# MainSheet.net
KiCad netlist of a schematic drawn in Altium Designer
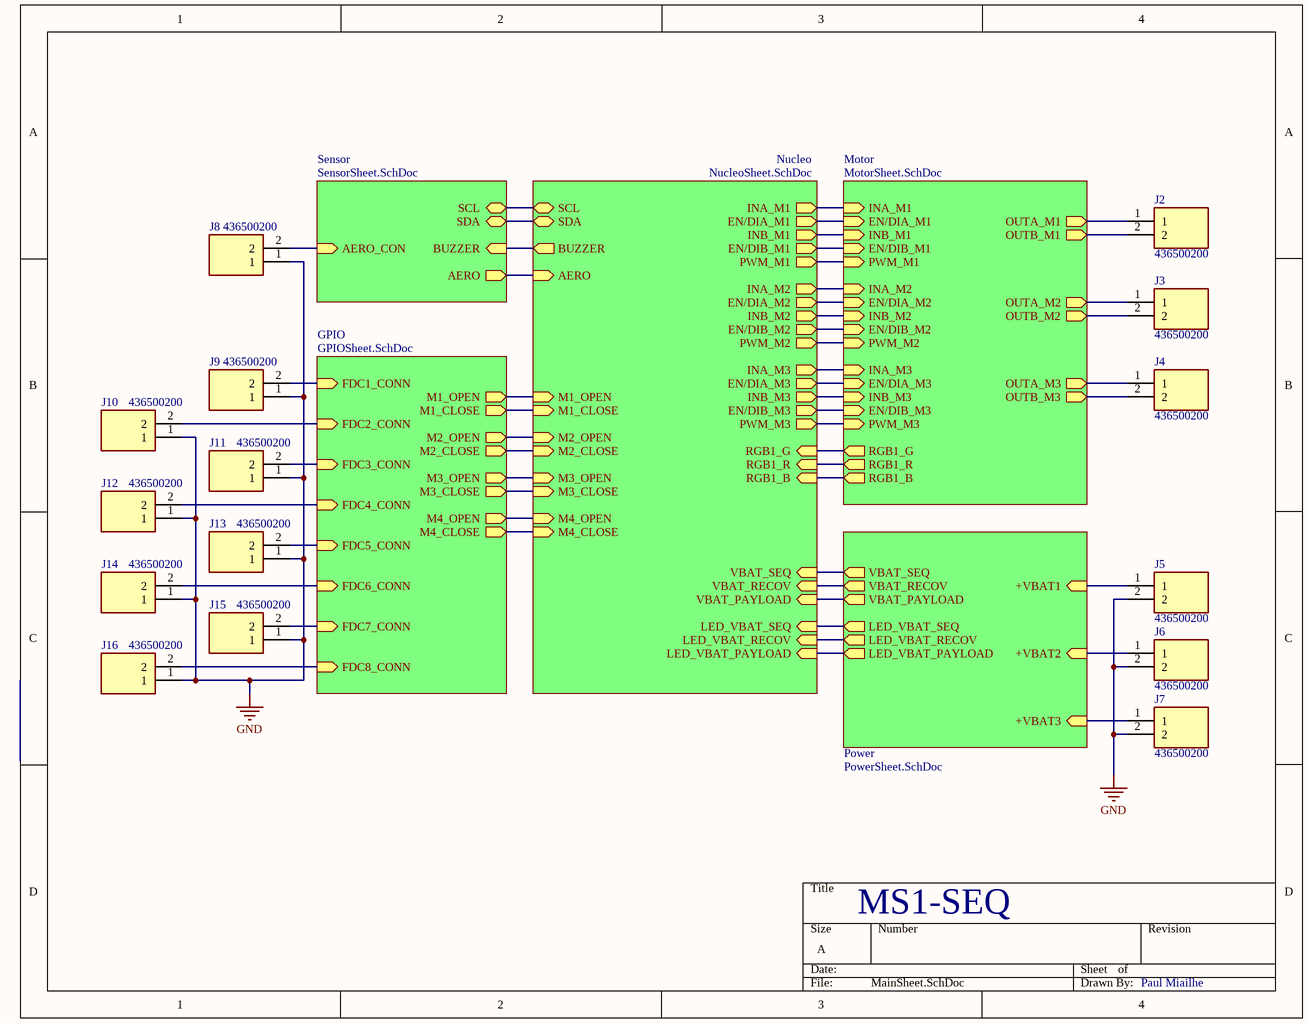
[diagram p0: MainSheet.SchDoc]

(export (version "E")
  (design (tool "Eeschema 10.0.6"))
  (components
    (comp (ref "J2")
      (value "436500200")
      (footprint "43650-0200:MOLEX_436500200")
      (fields (field (name "MF") "{'manufacturer': u'Molex'}"))
      (libsource (lib "*") (part "436500200"))
    )
    (comp (ref "J3")
      (value "436500200")
      (footprint "43650-0200:MOLEX_436500200")
      (fields (field (name "MF") "{'manufacturer': u'Molex'}"))
      (libsource (lib "*") (part "436500200"))
    )
    (comp (ref "J4")
      (value "436500200")
      (footprint "43650-0200:MOLEX_436500200")
      (fields (field (name "MF") "{'manufacturer': u'Molex'}"))
      (libsource (lib "*") (part "436500200"))
    )
    (comp (ref "J5")
      (value "436500200")
      (footprint "43650-0200:MOLEX_436500200")
      (fields (field (name "MF") "{'manufacturer': u'Molex'}"))
      (libsource (lib "*") (part "436500200"))
    )
    (comp (ref "J6")
      (value "436500200")
      (footprint "43650-0200:MOLEX_436500200")
      (fields (field (name "MF") "{'manufacturer': u'Molex'}"))
      (libsource (lib "*") (part "436500200"))
    )
    (comp (ref "J7")
      (value "436500200")
      (footprint "43650-0200:MOLEX_436500200")
      (fields (field (name "MF") "{'manufacturer': u'Molex'}"))
      (libsource (lib "*") (part "436500200"))
    )
    (comp (ref "J8")
      (value "436500200")
      (footprint "43650-0200:MOLEX_436500200")
      (fields (field (name "MF") "{'manufacturer': u'Molex'}"))
      (libsource (lib "") (part "436500200_1"))
    )
    (comp (ref "J9")
      (value "436500200")
      (footprint "43650-0200:MOLEX_436500200")
      (fields (field (name "MF") "{'manufacturer': u'Molex'}"))
      (libsource (lib "") (part "436500200_1"))
    )
    (comp (ref "J10")
      (value "436500200")
      (footprint "43650-0200:MOLEX_436500200")
      (fields (field (name "MF") "{'manufacturer': u'Molex'}"))
      (libsource (lib "") (part "436500200_1"))
    )
    (comp (ref "J11")
      (value "436500200")
      (footprint "43650-0200:MOLEX_436500200")
      (fields (field (name "MF") "{'manufacturer': u'Molex'}"))
      (libsource (lib "") (part "436500200_1"))
    )
    (comp (ref "J12")
      (value "436500200")
      (footprint "43650-0200:MOLEX_436500200")
      (fields (field (name "MF") "{'manufacturer': u'Molex'}"))
      (libsource (lib "") (part "436500200_1"))
    )
    (comp (ref "J13")
      (value "436500200")
      (footprint "43650-0200:MOLEX_436500200")
      (fields (field (name "MF") "{'manufacturer': u'Molex'}"))
      (libsource (lib "") (part "436500200_1"))
    )
    (comp (ref "J14")
      (value "436500200")
      (footprint "43650-0200:MOLEX_436500200")
      (fields (field (name "MF") "{'manufacturer': u'Molex'}"))
      (libsource (lib "") (part "436500200_1"))
    )
    (comp (ref "J15")
      (value "436500200")
      (footprint "43650-0200:MOLEX_436500200")
      (fields (field (name "MF") "{'manufacturer': u'Molex'}"))
      (libsource (lib "") (part "436500200_1"))
    )
    (comp (ref "J16")
      (value "436500200")
      (footprint "43650-0200:MOLEX_436500200")
      (fields (field (name "MF") "{'manufacturer': u'Molex'}"))
      (libsource (lib "") (part "436500200_1"))
    )
  )
  (nets
    (net (code "1") (name "/+VBAT1") (class "Default")
      (node (ref "J5") (pin "1") (pinfunction "1_1") (pintype "passive"))
    )
    (net (code "2") (name "/+VBAT2") (class "Default")
      (node (ref "J6") (pin "1") (pinfunction "1_1") (pintype "passive"))
    )
    (net (code "3") (name "/+VBAT3") (class "Default")
      (node (ref "J7") (pin "1") (pinfunction "1_1") (pintype "passive"))
    )
    (net (code "5") (name "/AERO_CON") (class "Default")
      (node (ref "J8") (pin "2") (pinfunction "2_2") (pintype "passive"))
    )
    (net (code "13") (name "/FDC1_CONN") (class "Default")
      (node (ref "J9") (pin "2") (pinfunction "2_2") (pintype "passive"))
    )
    (net (code "14") (name "/FDC2_CONN") (class "Default")
      (node (ref "J10") (pin "2") (pinfunction "2_2") (pintype "passive"))
    )
    (net (code "15") (name "/FDC3_CONN") (class "Default")
      (node (ref "J11") (pin "2") (pinfunction "2_2") (pintype "passive"))
    )
    (net (code "16") (name "/FDC4_CONN") (class "Default")
      (node (ref "J12") (pin "2") (pinfunction "2_2") (pintype "passive"))
    )
    (net (code "17") (name "/FDC5_CONN") (class "Default")
      (node (ref "J13") (pin "2") (pinfunction "2_2") (pintype "passive"))
    )
    (net (code "18") (name "/FDC6_CONN") (class "Default")
      (node (ref "J14") (pin "2") (pinfunction "2_2") (pintype "passive"))
    )
    (net (code "19") (name "/FDC7_CONN") (class "Default")
      (node (ref "J15") (pin "2") (pinfunction "2_2") (pintype "passive"))
    )
    (net (code "20") (name "/FDC8_CONN") (class "Default")
      (node (ref "J16") (pin "2") (pinfunction "2_2") (pintype "passive"))
    )
    (net (code "38") (name "/OUTA_M1") (class "Default")
      (node (ref "J2") (pin "1") (pinfunction "1_1") (pintype "passive"))
    )
    (net (code "39") (name "/OUTA_M2") (class "Default")
      (node (ref "J3") (pin "1") (pinfunction "1_1") (pintype "passive"))
    )
    (net (code "40") (name "/OUTA_M3") (class "Default")
      (node (ref "J4") (pin "1") (pinfunction "1_1") (pintype "passive"))
    )
    (net (code "41") (name "/OUTB_M1") (class "Default")
      (node (ref "J2") (pin "2") (pinfunction "2_2") (pintype "passive"))
    )
    (net (code "42") (name "/OUTB_M2") (class "Default")
      (node (ref "J3") (pin "2") (pinfunction "2_2") (pintype "passive"))
    )
    (net (code "43") (name "/OUTB_M3") (class "Default")
      (node (ref "J4") (pin "2") (pinfunction "2_2") (pintype "passive"))
    )
    (net (code "55") (name "GND") (class "Default")
      (node (ref "J10") (pin "1") (pinfunction "1_1") (pintype "passive"))
      (node (ref "J11") (pin "1") (pinfunction "1_1") (pintype "passive"))
      (node (ref "J12") (pin "1") (pinfunction "1_1") (pintype "passive"))
      (node (ref "J13") (pin "1") (pinfunction "1_1") (pintype "passive"))
      (node (ref "J14") (pin "1") (pinfunction "1_1") (pintype "passive"))
      (node (ref "J15") (pin "1") (pinfunction "1_1") (pintype "passive"))
      (node (ref "J16") (pin "1") (pinfunction "1_1") (pintype "passive"))
      (node (ref "J5") (pin "2") (pinfunction "2_2") (pintype "passive"))
      (node (ref "J6") (pin "2") (pinfunction "2_2") (pintype "passive"))
      (node (ref "J7") (pin "2") (pinfunction "2_2") (pintype "passive"))
      (node (ref "J8") (pin "1") (pinfunction "1_1") (pintype "passive"))
      (node (ref "J9") (pin "1") (pinfunction "1_1") (pintype "passive"))
    )
  )
)
